# Power_Supply.net
KiCad netlist of a schematic drawn in Altium Designer
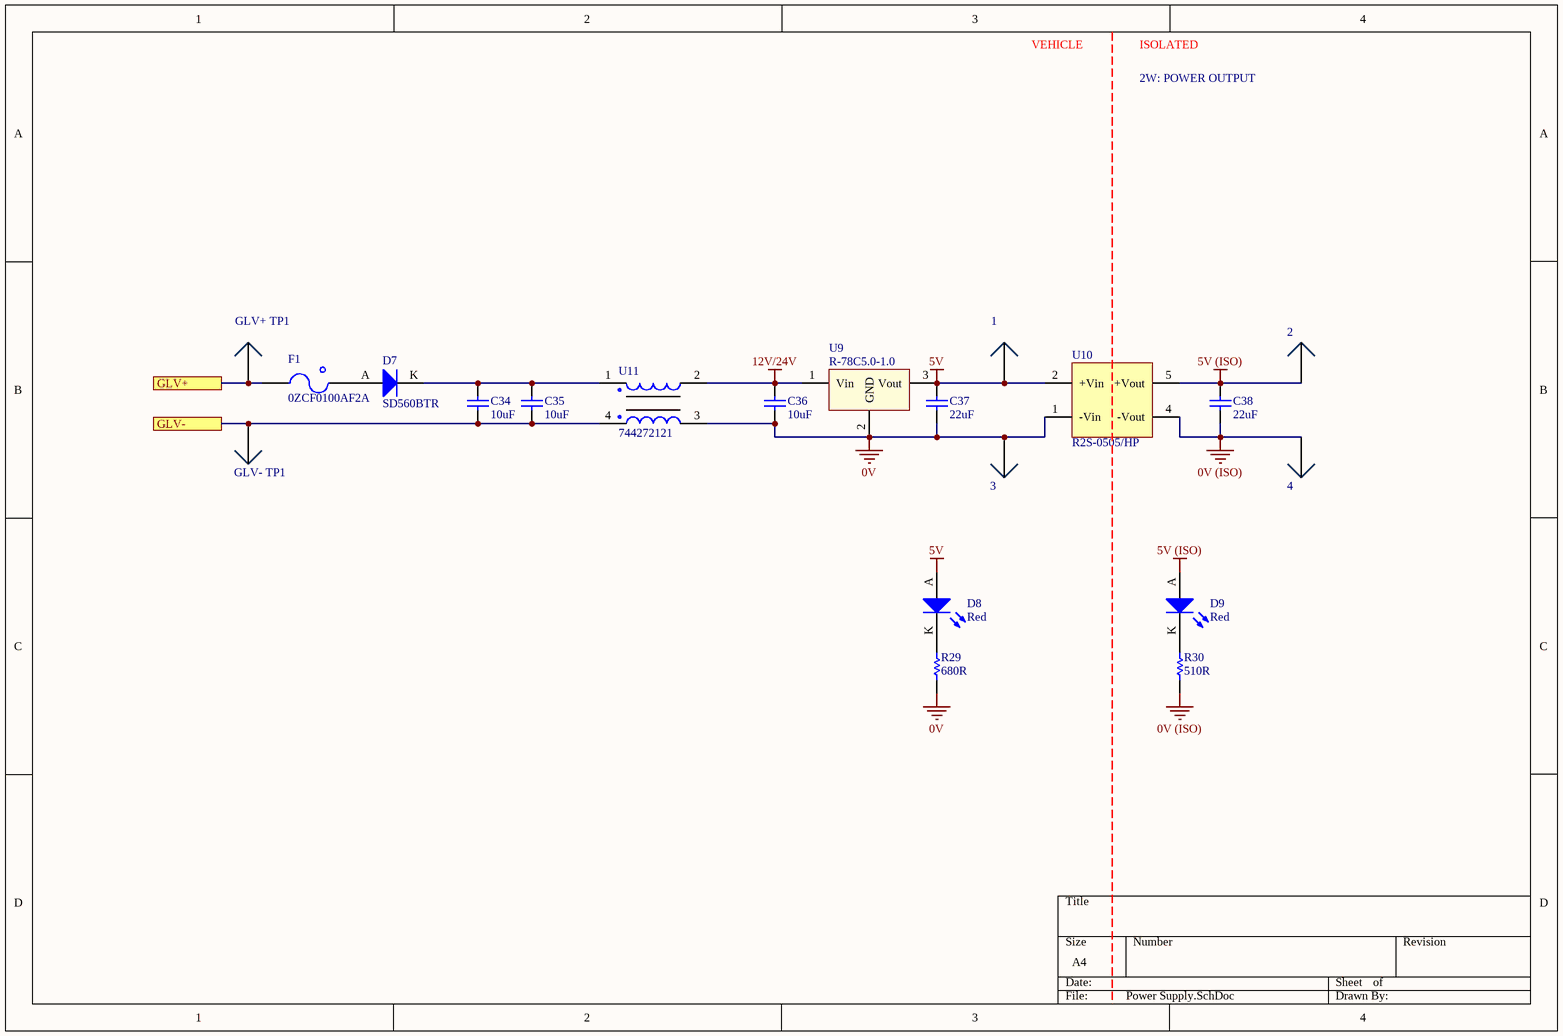
[diagram p0: Power Supply.SchDoc]

(export (version "E")
  (design (tool "Eeschema 10.0.6"))
  (components
    (comp (ref "1")
      (value "0mm")
      (footprint "SMD Test Point")
      (fields (field (name "PART NUMBER") "SMD Test Point") (field (name "CONTACT") "NA"))
      (libsource (lib "ts_20-standard-connectors") (part "Test Point"))
    )
    (comp (ref "2")
      (value "0mm")
      (footprint "SMD Test Point")
      (fields (field (name "PART NUMBER") "SMD Test Point") (field (name "CONTACT") "NA"))
      (libsource (lib "ts_20-standard-connectors") (part "Test Point"))
    )
    (comp (ref "3")
      (value "0mm")
      (footprint "SMD Test Point")
      (fields (field (name "PART NUMBER") "SMD Test Point") (field (name "CONTACT") "NA"))
      (libsource (lib "ts_20-standard-connectors") (part "Test Point"))
    )
    (comp (ref "4")
      (value "0mm")
      (footprint "SMD Test Point")
      (fields (field (name "PART NUMBER") "SMD Test Point") (field (name "CONTACT") "NA"))
      (libsource (lib "ts_20-standard-connectors") (part "Test Point"))
    )
    (comp (ref "C34")
      (value "10uF")
      (footprint "0805")
      (fields
        (field (name "PART NUMBER") "GRM21BR6YA106KE43L")
        (field (name "TOLERANCE") "10%")
        (field (name "MANUFACTURER") "muRata")
      )
      (libsource (lib "ts_20-standard-library") (part "Capacitor"))
    )
    (comp (ref "C35")
      (value "10uF")
      (footprint "0805")
      (fields
        (field (name "PART NUMBER") "GRM21BR6YA106KE43L")
        (field (name "TOLERANCE") "10%")
        (field (name "MANUFACTURER") "muRata")
      )
      (libsource (lib "ts_20-standard-library") (part "Capacitor"))
    )
    (comp (ref "C36")
      (value "10uF")
      (footprint "0805")
      (fields
        (field (name "PART NUMBER") "GRM21BR6YA106KE43L")
        (field (name "TOLERANCE") "10%")
        (field (name "MANUFACTURER") "muRata")
      )
      (libsource (lib "ts_20-standard-library") (part "Capacitor"))
    )
    (comp (ref "C37")
      (value "22uF")
      (footprint "1206")
      (fields
        (field (name "PART NUMBER") "CC1206MKX5R7BB226")
        (field (name "TOLERANCE") "20%")
        (field (name "MANUFACTURER") "YAGEO")
      )
      (libsource (lib "ts_20-standard-library") (part "Capacitor"))
    )
    (comp (ref "C38")
      (value "22uF")
      (footprint "1206")
      (fields
        (field (name "PART NUMBER") "CC1206MKX5R7BB226")
        (field (name "TOLERANCE") "20%")
        (field (name "MANUFACTURER") "YAGEO")
      )
      (libsource (lib "ts_20-standard-library") (part "Capacitor"))
    )
    (comp (ref "D7")
      (value "SD560BTR")
      (footprint "SMB Diode")
      (description "1.2V_F 600V 5A SMB")
      (fields
        (field (name "MANUFACTURER") "SMC Diode Solutions")
        (field (name "DIGIKEY PART NUMBER") "1655-1530-2-ND")
      )
      (libsource (lib "ts_20-standard-library") (part "Diode"))
    )
    (comp (ref "D8")
      (value "Red")
      (footprint "0805 LED")
      (description "Red LED Indication - Discrete 1.75V 0805 (2012 Metric)")
      (fields (field (name "PART NUMBER") "SML-210LTT86") (field (name "MANUFACTURER") "ROHM Semiconductor"))
      (libsource (lib "ts_20-standard-library") (part "LED"))
    )
    (comp (ref "D9")
      (value "Red")
      (footprint "0805 LED")
      (description "Red LED Indication - Discrete 1.75V 0805 (2012 Metric)")
      (fields (field (name "PART NUMBER") "SML-210LTT86") (field (name "MANUFACTURER") "ROHM Semiconductor"))
      (libsource (lib "ts_20-standard-library") (part "LED"))
    )
    (comp (ref "F1")
      (value "0ZCF0100AF2A")
      (footprint "2920")
      (description "PTC RESET FUSE 60V 1A 292")
      (fields
        (field (name "MANUFACTURER") "Littelfuse Inc.")
        (field (name "DIGIKEY PART NUMBER") "507-2070-1-ND")
      )
      (libsource (lib "ts_20-standard-library") (part "PTC Fuse"))
    )
    (comp (ref "GLV+ TP1")
      (value "0mm")
      (footprint "SMD Test Point")
      (fields (field (name "PART NUMBER") "SMD Test Point") (field (name "CONTACT") "NA"))
      (libsource (lib "ts_20-standard-connectors") (part "Test Point"))
    )
    (comp (ref "GLV- TP1")
      (value "0mm")
      (footprint "SMD Test Point")
      (fields (field (name "PART NUMBER") "SMD Test Point") (field (name "CONTACT") "NA"))
      (libsource (lib "ts_20-standard-connectors") (part "Test Point"))
    )
    (comp (ref "R29")
      (value "680R")
      (footprint "0805")
      (fields
        (field (name "PART NUMBER") "RC0805FR07680RL")
        (field (name "MANUFACTURER") "YAGEO")
        (field (name "TOLERANCE") "0.01")
      )
      (libsource (lib "ts_20-standard-library") (part "Resistor"))
    )
    (comp (ref "R30")
      (value "510R")
      (footprint "0805")
      (fields
        (field (name "PART NUMBER") "RC0805FR07510RL")
        (field (name "MANUFACTURER") "YAGEO")
        (field (name "TOLERANCE") "0.01")
      )
      (libsource (lib "ts_20-standard-library") (part "Resistor"))
    )
    (comp (ref "U9")
      (value "R-78C5.0-1.0")
      (footprint "RECOM 3-SIP")
      (description "CONV DC/DC 1A 5V OUT SIP VERT")
      (fields (field (name "MANUFACTURER") "Recom") (field (name "DIGIKEY PART NUMBER") "945-1395-5-ND"))
      (libsource (lib "ts_20-standard-library") (part "R-78C5.0-1.0"))
    )
    (comp (ref "U10")
      (value "R2S-0505/HP")
      (footprint "RECOM 8-SMD (5 Pin)")
      (description "Isolated Module DC DC Converter 1 Output 3.3V 606mA 4.5V - 5.5V Input")
      (fields (field (name "MANUFACTURER") "Recom") (field (name "DIGIKEY PART NUMBER") "945-1764-5-ND"))
      (libsource (lib "ts_20-standard-library") (part "R2S-0505/HP"))
    )
    (comp (ref "U11")
      (value "744272121")
      (footprint "Wurth 4-PC Pad")
      (description "120µH @ 100kHz 2 Line Common Mode Choke Surface Mount 460 Ohms @ 30MHz 2.5A DCR 25mOhm")
      (fields
        (field (name "MANUFACTURER") "Wurth Electronics Inc")
        (field (name "DIGIKEY PART NUMBER") "732-1489-1-ND")
      )
      (libsource (lib "ts_20-standard-library") (part "744272121"))
    )
  )
  (nets
    (net (code "1") (name "/GLV+") (class "Default")
      (node (ref "F1") (pin "1") (pinfunction "1_1") (pintype "passive"))
      (node (ref "GLV+ TP1") (pin "1") (pinfunction "1_1") (pintype "passive"))
    )
    (net (code "2") (name "/GLV-") (class "Default")
      (node (ref "C34") (pin "1") (pinfunction "1_1") (pintype "passive"))
      (node (ref "C35") (pin "1") (pinfunction "1_1") (pintype "passive"))
      (node (ref "GLV- TP1") (pin "1") (pinfunction "1_1") (pintype "passive"))
      (node (ref "U11") (pin "4") (pinfunction "4_4") (pintype "passive"))
    )
    (net (code "3") (name "0V") (class "Default")
      (node (ref "3") (pin "1") (pinfunction "1_1") (pintype "passive"))
      (node (ref "C36") (pin "1") (pinfunction "1_1") (pintype "passive"))
      (node (ref "C37") (pin "1") (pinfunction "1_1") (pintype "passive"))
      (node (ref "R29") (pin "1") (pinfunction "1_1") (pintype "passive"))
      (node (ref "U10") (pin "1") (pinfunction "-Vin_1") (pintype "power_in"))
      (node (ref "U11") (pin "3") (pinfunction "3_3") (pintype "power_in"))
      (node (ref "U9") (pin "2") (pinfunction "GND_2") (pintype "passive"))
    )
    (net (code "4") (name "0V (ISO)") (class "Default")
      (node (ref "4") (pin "1") (pinfunction "1_1") (pintype "passive"))
      (node (ref "C38") (pin "1") (pinfunction "1_1") (pintype "passive"))
      (node (ref "R30") (pin "1") (pinfunction "1_1") (pintype "passive"))
      (node (ref "U10") (pin "4") (pinfunction "-Vout_4") (pintype "power_in"))
    )
    (net (code "5") (name "5V") (class "Default")
      (node (ref "1") (pin "1") (pinfunction "1_1") (pintype "passive"))
      (node (ref "C37") (pin "2") (pinfunction "2_2") (pintype "passive"))
      (node (ref "D8") (pin "A") (pinfunction "A_A") (pintype "passive"))
      (node (ref "U10") (pin "2") (pinfunction "+Vin_2") (pintype "power_in"))
      (node (ref "U9") (pin "3") (pinfunction "Vout_3") (pintype "passive"))
    )
    (net (code "6") (name "5V (ISO)") (class "Default")
      (node (ref "2") (pin "1") (pinfunction "1_1") (pintype "passive"))
      (node (ref "C38") (pin "2") (pinfunction "2_2") (pintype "passive"))
      (node (ref "D9") (pin "A") (pinfunction "A_A") (pintype "passive"))
      (node (ref "U10") (pin "5") (pinfunction "+Vout_5") (pintype "power_in"))
    )
    (net (code "7") (name "12V{slash}24V") (class "Default")
      (node (ref "C36") (pin "2") (pinfunction "2_2") (pintype "passive"))
      (node (ref "U11") (pin "2") (pinfunction "2_2") (pintype "passive"))
      (node (ref "U9") (pin "1") (pinfunction "Vin_1") (pintype "passive"))
    )
    (net (code "8") (name "Net-(C34-Pad2)") (class "Default")
      (node (ref "C34") (pin "2") (pinfunction "2_2") (pintype "passive"))
      (node (ref "C35") (pin "2") (pinfunction "2_2") (pintype "passive"))
      (node (ref "D7") (pin "K") (pinfunction "K_K") (pintype "passive"))
      (node (ref "U11") (pin "1") (pinfunction "1_1") (pintype "passive"))
    )
    (net (code "9") (name "Net-(D7-PadA)") (class "Default")
      (node (ref "D7") (pin "A") (pinfunction "A_A") (pintype "passive"))
      (node (ref "F1") (pin "2") (pinfunction "2_2") (pintype "passive"))
    )
    (net (code "10") (name "Net-(D8-PadK)") (class "Default")
      (node (ref "D8") (pin "K") (pinfunction "K_K") (pintype "passive"))
      (node (ref "R29") (pin "2") (pinfunction "2_2") (pintype "passive"))
    )
    (net (code "11") (name "Net-(D9-PadK)") (class "Default")
      (node (ref "D9") (pin "K") (pinfunction "K_K") (pintype "passive"))
      (node (ref "R30") (pin "2") (pinfunction "2_2") (pintype "passive"))
    )
  )
)
